# Input.net
KiCad netlist of a schematic drawn in Altium Designer
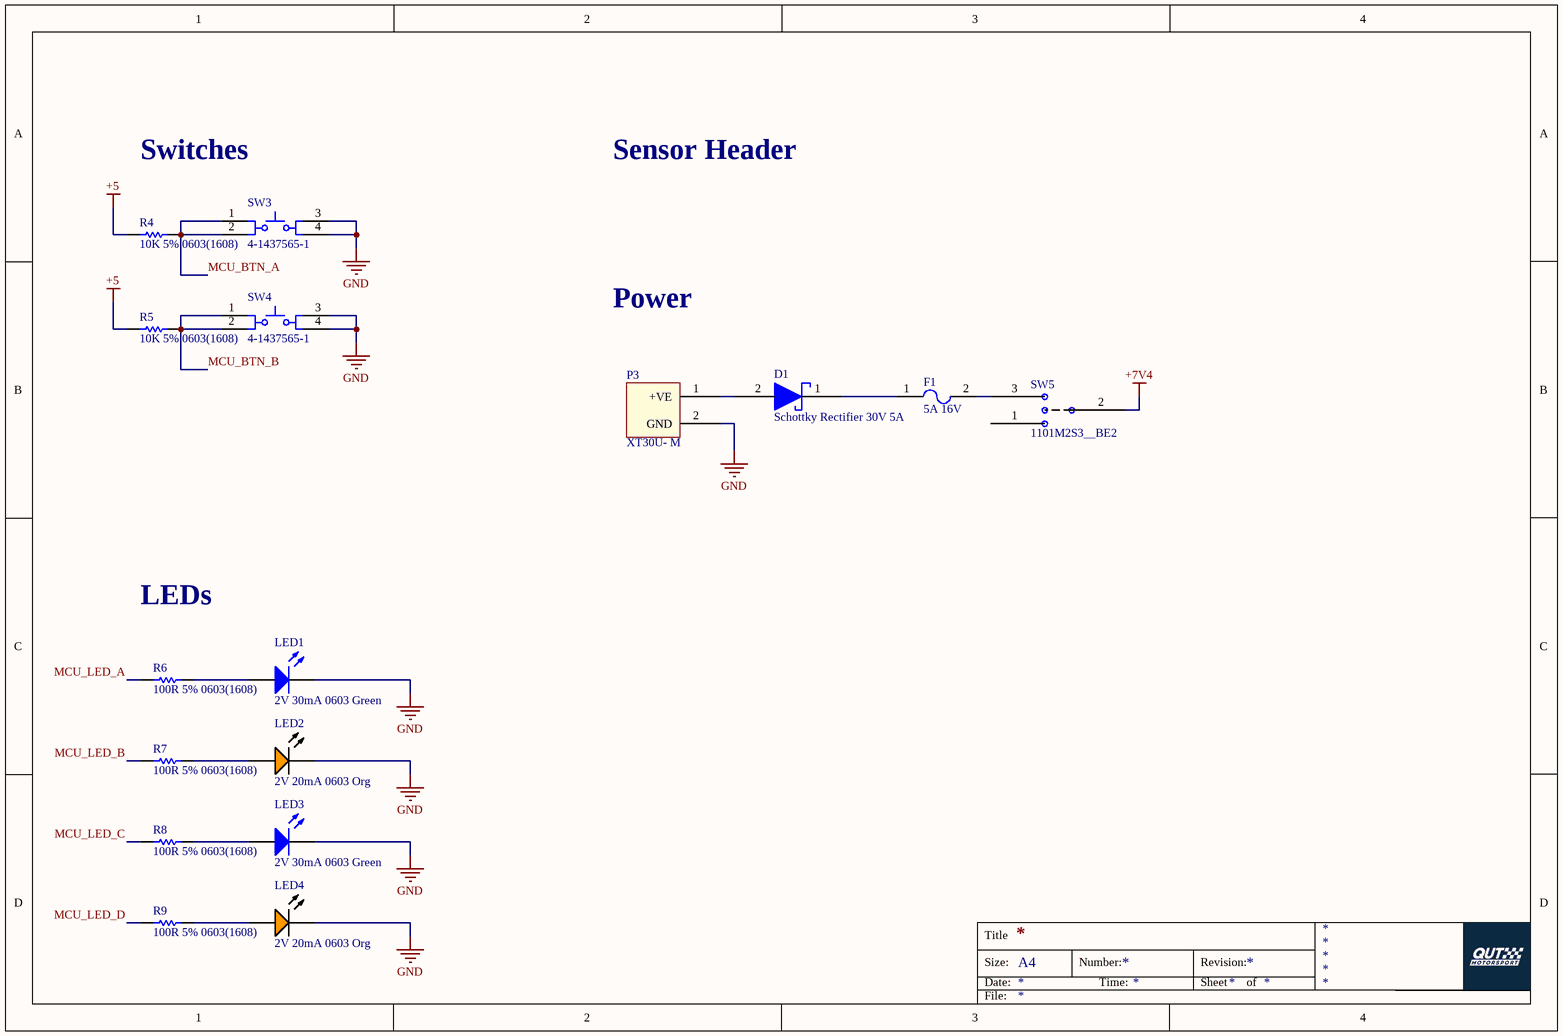
[diagram p0: Input.SchDoc]

(export (version "E")
  (design (tool "Eeschema 10.0.6"))
  (components
    (comp (ref "D1")
      (value "Schottky Rectifier 30V 5A")
      (footprint "Schottky Diode 30V 5A")
      (libsource (lib "EGB220") (part "Schottky Rectifier 30V 5A"))
    )
    (comp (ref "F1")
      (value "5A 16V")
      (footprint "Fuse 5A 16V 1812")
      (libsource (lib "EGB220") (part "Fuse 16V 5A 1812"))
    )
    (comp (ref "LED1")
      (value "2V 30mA 0603 Green")
      (footprint "0603_A")
      (description "SMD mono-color Chip LED, WL-SMCW, Bright Green")
      (fields (field (name "PARTNUMBER") "150060VS75000") (field (name "MANUFACTURER") "Wuerth Elektronik"))
      (libsource (lib "Altium Content Vault") (part "WE-LED_K1A2-2"))
    )
    (comp (ref "LED2")
      (value "2V 20mA 0603 Org")
      (footprint "KING-LED0603-25-ORANGE_V")
      (description "LED, SMT, 0603(1608), 0.25mm Tthickness, Super Bright Orange")
      (fields (field (name "PARTNUMBER") "APG1608SEKC/T"))
      (libsource (lib "Altium Content Vault") (part "KING-LED_ORANGE_A1K2-2"))
    )
    (comp (ref "LED3")
      (value "2V 30mA 0603 Green")
      (footprint "0603_A")
      (description "SMD mono-color Chip LED, WL-SMCW, Bright Green")
      (fields (field (name "PARTNUMBER") "150060VS75000") (field (name "MANUFACTURER") "Wuerth Elektronik"))
      (libsource (lib "Altium Content Vault") (part "WE-LED_K1A2-2"))
    )
    (comp (ref "LED4")
      (value "2V 20mA 0603 Org")
      (footprint "KING-LED0603-25-ORANGE_V")
      (description "LED, SMT, 0603(1608), 0.25mm Tthickness, Super Bright Orange")
      (fields (field (name "PARTNUMBER") "APG1608SEKC/T"))
      (libsource (lib "Altium Content Vault") (part "KING-LED_ORANGE_A1K2-2"))
    )
    (comp (ref "P3") (value "XT30U- M") (footprint "XT30U-M") (libsource (lib "EGB220") (part "XT30U- M")))
    (comp (ref "R4")
      (value "10K 5% 0603(1608)")
      (footprint "RESC0603(1608)_N")
      (description "10K 0.1W 5% 0603 (1608 Metric)  SMD")
      (fields (field (name "TOLERANCE") "5 %") (field (name "POWER") "0.1 W"))
      (libsource (lib "Altium Content Vault") (part "RES"))
    )
    (comp (ref "R5")
      (value "10K 5% 0603(1608)")
      (footprint "RESC0603(1608)_N")
      (description "10K 0.1W 5% 0603 (1608 Metric)  SMD")
      (fields (field (name "TOLERANCE") "5 %") (field (name "POWER") "0.1 W"))
      (libsource (lib "Altium Content Vault") (part "RES"))
    )
    (comp (ref "R6")
      (value "100R 5% 0603(1608)")
      (footprint "RESC0603(1608)_L")
      (description "100R 0.1W 5% 0603 (1608 Metric)  SMD")
      (fields (field (name "TOLERANCE") "5 %") (field (name "POWER") "0.1 W"))
      (libsource (lib "Altium Content Vault") (part "RES"))
    )
    (comp (ref "R7")
      (value "100R 5% 0603(1608)")
      (footprint "RESC0603(1608)_L")
      (description "100R 0.1W 5% 0603 (1608 Metric)  SMD")
      (fields (field (name "TOLERANCE") "5 %") (field (name "POWER") "0.1 W"))
      (libsource (lib "Altium Content Vault") (part "RES"))
    )
    (comp (ref "R8")
      (value "100R 5% 0603(1608)")
      (footprint "RESC0603(1608)_L")
      (description "100R 0.1W 5% 0603 (1608 Metric)  SMD")
      (fields (field (name "TOLERANCE") "5 %") (field (name "POWER") "0.1 W"))
      (libsource (lib "Altium Content Vault") (part "RES"))
    )
    (comp (ref "R9")
      (value "100R 5% 0603(1608)")
      (footprint "RESC0603(1608)_L")
      (description "100R 0.1W 5% 0603 (1608 Metric)  SMD")
      (fields (field (name "TOLERANCE") "5 %") (field (name "POWER") "0.1 W"))
      (libsource (lib "Altium Content Vault") (part "RES"))
    )
    (comp (ref "SW3")
      (value "4-1437565-1")
      (footprint "TECO-4-1437565-1_V")
      (description "Tactile Switch, 50 mA, 12 VDC, -20 to 85 degC, 4-Pin SMD, RoHS, Bulk")
      (fields (field (name "MANUFACTURER") "TEConnectivity/AMPBrand"))
      (libsource (lib "Altium Content Vault") (part "SW-SPST-NO-4"))
    )
    (comp (ref "SW4")
      (value "4-1437565-1")
      (footprint "TECO-4-1437565-1_V")
      (description "Tactile Switch, 50 mA, 12 VDC, -20 to 85 degC, 4-Pin SMD, RoHS, Bulk")
      (fields (field (name "MANUFACTURER") "TEConnectivity/AMPBrand"))
      (libsource (lib "Altium Content Vault") (part "SW-SPST-NO-4"))
    )
    (comp (ref "SW5")
      (value "1101M2S3__BE2")
      (footprint "1101M2S3__BE2")
      (libsource (lib "EGB220") (part "1101M2S3__BE2"))
    )
  )
  (nets
    (net (code "1") (name "+5") (class "Default")
      (node (ref "R4") (pin "2") (pinfunction "2_2") (pintype "passive"))
      (node (ref "R5") (pin "2") (pinfunction "2_2") (pintype "passive"))
    )
    (net (code "2") (name "+7V4") (class "Default")
      (node (ref "SW5") (pin "2") (pinfunction "2_2") (pintype "passive"))
    )
    (net (code "3") (name "/MCU_BTN_A") (class "Default")
      (node (ref "R4") (pin "1") (pinfunction "1_1") (pintype "passive"))
      (node (ref "SW3") (pin "1") (pinfunction "1_1") (pintype "passive"))
      (node (ref "SW3") (pin "2") (pinfunction "2_2") (pintype "passive"))
    )
    (net (code "4") (name "/MCU_BTN_B") (class "Default")
      (node (ref "R5") (pin "1") (pinfunction "1_1") (pintype "passive"))
      (node (ref "SW4") (pin "1") (pinfunction "1_1") (pintype "passive"))
      (node (ref "SW4") (pin "2") (pinfunction "2_2") (pintype "passive"))
    )
    (net (code "5") (name "/MCU_LED_A") (class "Default")
      (node (ref "R6") (pin "1") (pinfunction "1_1") (pintype "passive"))
    )
    (net (code "6") (name "/MCU_LED_B") (class "Default")
      (node (ref "R7") (pin "2") (pinfunction "2_2") (pintype "passive"))
    )
    (net (code "7") (name "/MCU_LED_C") (class "Default")
      (node (ref "R8") (pin "1") (pinfunction "1_1") (pintype "passive"))
    )
    (net (code "8") (name "/MCU_LED_D") (class "Default")
      (node (ref "R9") (pin "2") (pinfunction "2_2") (pintype "passive"))
    )
    (net (code "9") (name "GND") (class "Default")
      (node (ref "LED1") (pin "1") (pinfunction "K_1") (pintype "passive"))
      (node (ref "LED2") (pin "2") (pinfunction "K_2") (pintype "passive"))
      (node (ref "LED3") (pin "1") (pinfunction "K_1") (pintype "passive"))
      (node (ref "LED4") (pin "2") (pinfunction "K_2") (pintype "passive"))
      (node (ref "P3") (pin "2") (pinfunction "GND_2") (pintype "passive"))
      (node (ref "SW3") (pin "3") (pinfunction "3_3") (pintype "passive"))
      (node (ref "SW3") (pin "4") (pinfunction "4_4") (pintype "passive"))
      (node (ref "SW4") (pin "3") (pinfunction "3_3") (pintype "passive"))
      (node (ref "SW4") (pin "4") (pinfunction "4_4") (pintype "passive"))
    )
    (net (code "10") (name "Net-(D1-A)") (class "Default")
      (node (ref "D1") (pin "2") (pinfunction "A_2") (pintype "passive"))
      (node (ref "P3") (pin "1") (pinfunction "+VE_1") (pintype "passive"))
    )
    (net (code "11") (name "Net-(D1-K)") (class "Default")
      (node (ref "D1") (pin "1") (pinfunction "K_1") (pintype "passive"))
      (node (ref "F1") (pin "1") (pinfunction "1_1") (pintype "passive"))
    )
    (net (code "12") (name "Net-(F1-Pad2)") (class "Default")
      (node (ref "F1") (pin "2") (pinfunction "2_2") (pintype "passive"))
      (node (ref "SW5") (pin "3") (pinfunction "3_3") (pintype "passive"))
    )
    (net (code "13") (name "Net-(LED1-A)") (class "Default")
      (node (ref "LED1") (pin "2") (pinfunction "A_2") (pintype "passive"))
      (node (ref "R6") (pin "2") (pinfunction "2_2") (pintype "passive"))
    )
    (net (code "14") (name "Net-(LED2-A)") (class "Default")
      (node (ref "LED2") (pin "1") (pinfunction "A_1") (pintype "passive"))
      (node (ref "R7") (pin "1") (pinfunction "1_1") (pintype "passive"))
    )
    (net (code "15") (name "Net-(LED3-A)") (class "Default")
      (node (ref "LED3") (pin "2") (pinfunction "A_2") (pintype "passive"))
      (node (ref "R8") (pin "2") (pinfunction "2_2") (pintype "passive"))
    )
    (net (code "16") (name "Net-(LED4-A)") (class "Default")
      (node (ref "LED4") (pin "1") (pinfunction "A_1") (pintype "passive"))
      (node (ref "R9") (pin "1") (pinfunction "1_1") (pintype "passive"))
    )
    (net (code "17") (name "unconnected-(SW5-Pad1)") (class "Default")
      (node (ref "SW5") (pin "1") (pinfunction "1_1") (pintype "passive"))
    )
  )
)
